# radio-86rk-SRAM-sdcard.net
KiCad netlist of a schematic drawn in EAGLE
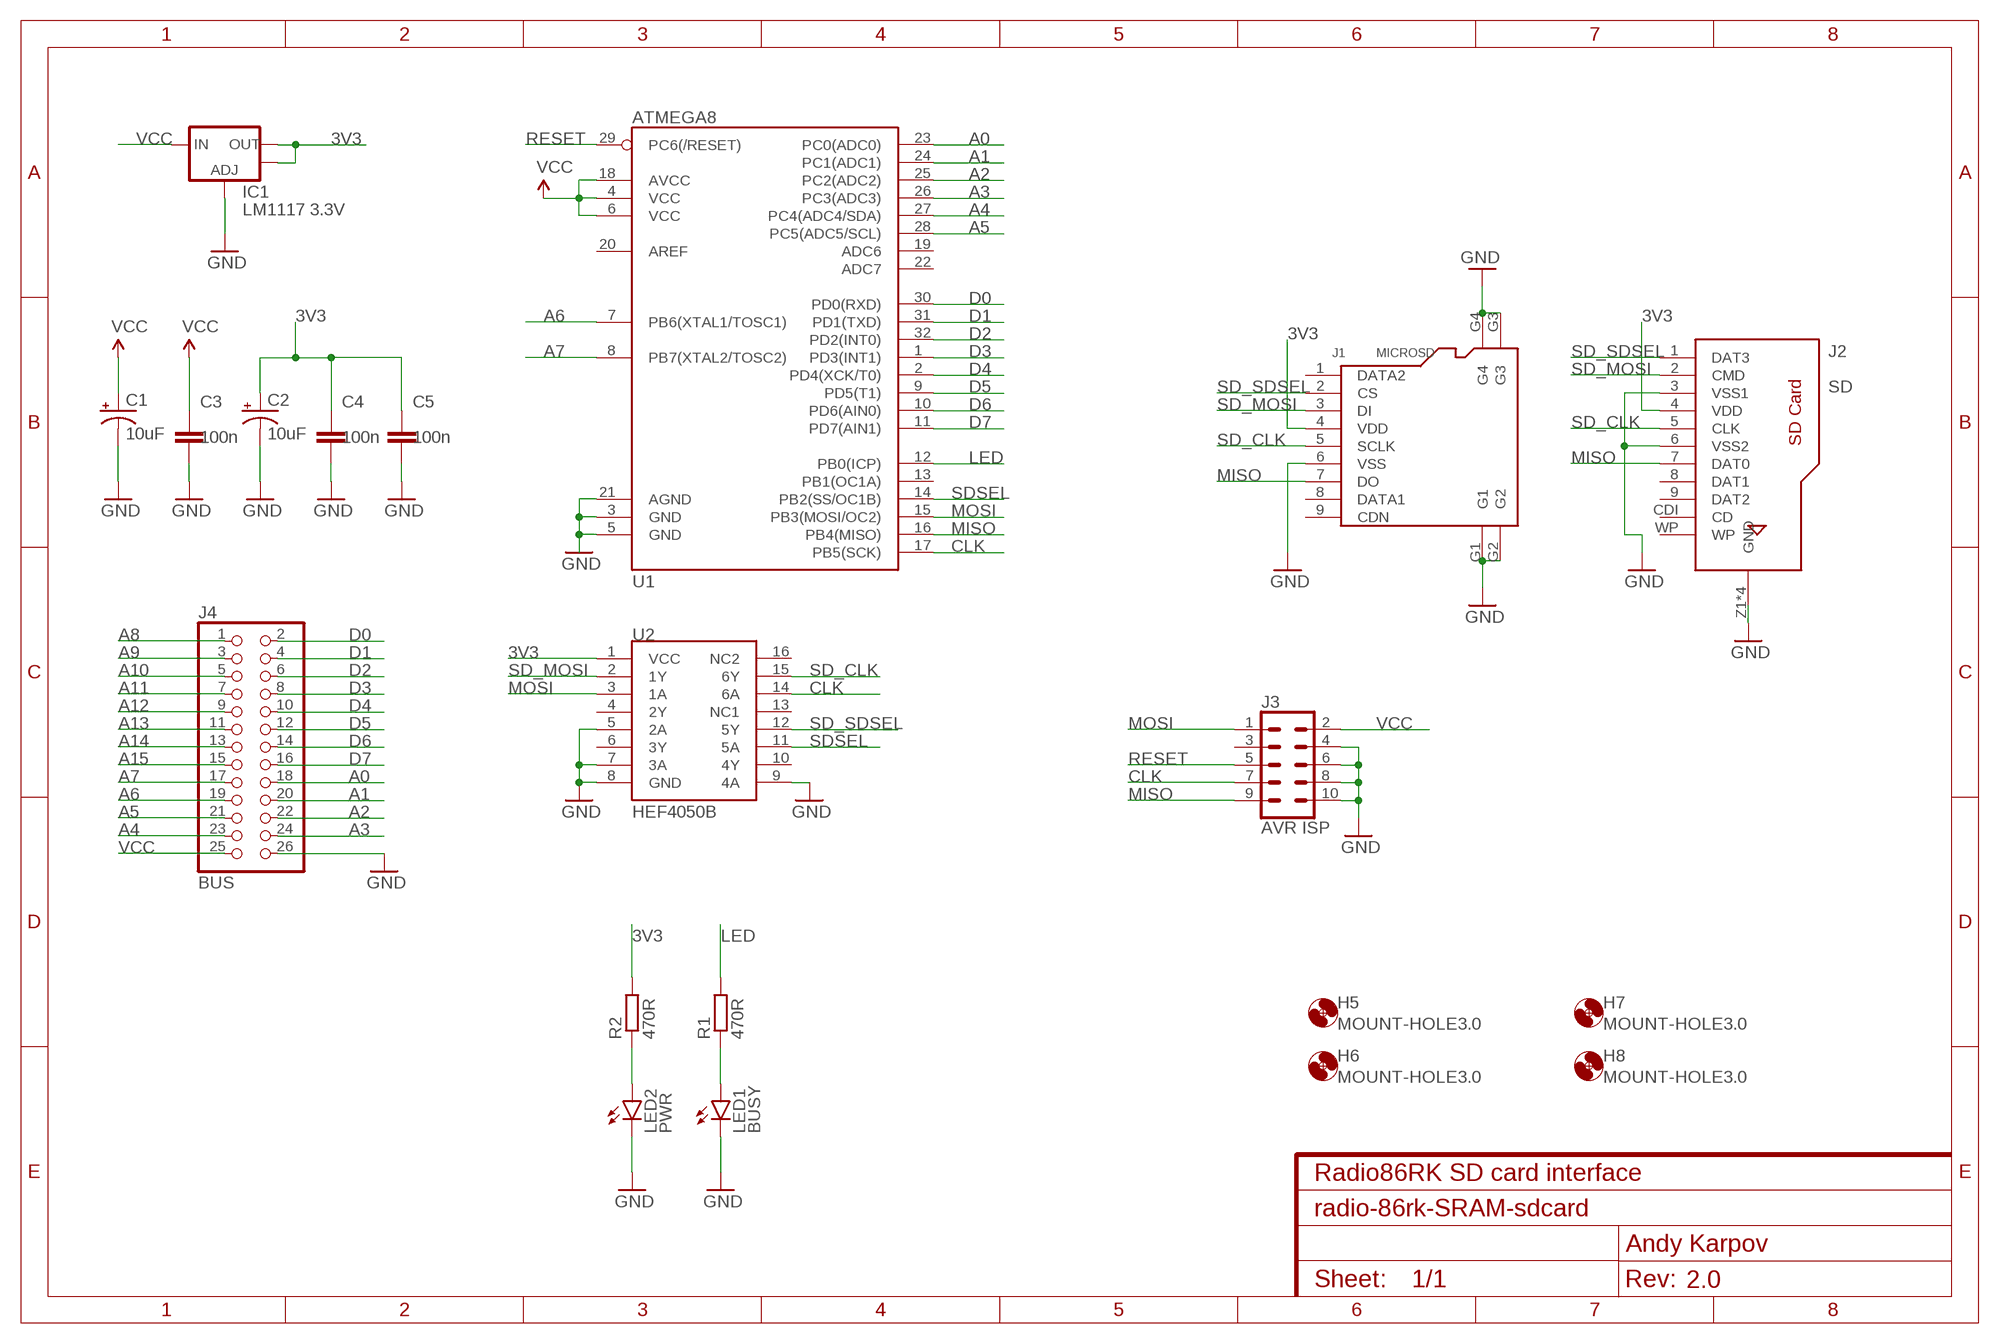
[diagram p0: schematic, sheet 1]

(export (version "E")
  (design (tool "Eeschema 10.0.6"))
  (components
    (comp (ref "C1")
      (value "10uF")
      (footprint "eagle-import:EIA3216")
      (libsource (lib "eagle-import") (part "10UF-16V-10%(TANT)"))
    )
    (comp (ref "C2")
      (value "10uF")
      (footprint "eagle-import:EIA3216")
      (libsource (lib "eagle-import") (part "10UF-16V-10%(TANT)"))
    )
    (comp (ref "C3")
      (value "100n")
      (footprint "eagle-import:C0805")
      (libsource (lib "eagle-import") (part "C-EUC0805"))
    )
    (comp (ref "C4")
      (value "100n")
      (footprint "eagle-import:C0805")
      (libsource (lib "eagle-import") (part "C-EUC0805"))
    )
    (comp (ref "C5")
      (value "100n")
      (footprint "eagle-import:C0805")
      (libsource (lib "eagle-import") (part "C-EUC0805"))
    )
    (comp (ref "H5")
      (value "MOUNT-HOLE3.0")
      (footprint "eagle-import:3,0")
      (libsource (lib "eagle-import") (part "MOUNT-HOLE3.0"))
    )
    (comp (ref "H6")
      (value "MOUNT-HOLE3.0")
      (footprint "eagle-import:3,0")
      (libsource (lib "eagle-import") (part "MOUNT-HOLE3.0"))
    )
    (comp (ref "H7")
      (value "MOUNT-HOLE3.0")
      (footprint "eagle-import:3,0")
      (libsource (lib "eagle-import") (part "MOUNT-HOLE3.0"))
    )
    (comp (ref "H8")
      (value "MOUNT-HOLE3.0")
      (footprint "eagle-import:3,0")
      (libsource (lib "eagle-import") (part "MOUNT-HOLE3.0"))
    )
    (comp (ref "IC1")
      (value "LM1117 3.3V")
      (footprint "eagle-import:SOT223")
      (libsource (lib "eagle-import") (part "V_REG_LM1117SOT223"))
    )
    (comp (ref "J1")
      (value "MICROSD")
      (footprint "eagle-import:MICRO-SD9+4P-SMD-16.1X14.5X1.85MM")
      (libsource (lib "eagle-import") (part "MICRO-SD-CARD-HOLDER-9P"))
    )
    (comp (ref "J2")
      (value "SD")
      (footprint "eagle-import:693063010911")
      (libsource (lib "eagle-import") (part "693063010911"))
    )
    (comp (ref "J3")
      (value "AVR ISP")
      (footprint "eagle-import:2X5-SHROUDED_LOCK")
      (libsource (lib "eagle-import") (part "CONN_05X2SHD_LOCK"))
    )
    (comp (ref "J4")
      (value "BUS")
      (footprint "eagle-import:2X13")
      (libsource (lib "eagle-import") (part "PINHD-2X13"))
    )
    (comp (ref "LED1")
      (value "BUSY")
      (footprint "eagle-import:CHIP-LED0805")
      (libsource (lib "eagle-import") (part "LEDCHIP-LED0805"))
    )
    (comp (ref "LED2")
      (value "PWR")
      (footprint "eagle-import:CHIP-LED0805")
      (libsource (lib "eagle-import") (part "LEDCHIP-LED0805"))
    )
    (comp (ref "R1")
      (value "470R")
      (footprint "eagle-import:R0805")
      (libsource (lib "eagle-import") (part "R-EU_R0805"))
    )
    (comp (ref "R2")
      (value "470R")
      (footprint "eagle-import:R0805")
      (libsource (lib "eagle-import") (part "R-EU_R0805"))
    )
    (comp (ref "U1")
      (value "ATMEGA8")
      (footprint "eagle-import:TQFP32-08")
      (libsource (lib "eagle-import") (part "ATMEGA328_SMT"))
    )
    (comp (ref "U2")
      (value "HEF4050B")
      (footprint "eagle-import:SO16")
      (libsource (lib "eagle-import") (part "HEF4050BSO16"))
    )
  )
  (nets
    (net (code "1") (name "/3V3") (class "Default")
      (node (ref "C2") (pin "A") (pinfunction "+_A") (pintype "passive"))
      (node (ref "C4") (pin "1") (pinfunction "1_1") (pintype "passive"))
      (node (ref "C5") (pin "1") (pinfunction "1_1") (pintype "passive"))
      (node (ref "IC1") (pin "2") (pinfunction "OUT_2") (pintype "output"))
      (node (ref "IC1") (pin "4") (pinfunction "OUT_4") (pintype "output"))
      (node (ref "J1") (pin "4") (pinfunction "VDD_4") (pintype "bidirectional"))
      (node (ref "J2") (pin "4") (pinfunction "VDD_4") (pintype "bidirectional"))
      (node (ref "R2") (pin "2") (pinfunction "2_2") (pintype "passive"))
      (node (ref "U2") (pin "1") (pinfunction "VCC_1") (pintype "power_in"))
    )
    (net (code "2") (name "/A0") (class "Default")
      (node (ref "J4") (pin "18") (pinfunction "18_18") (pintype "passive"))
      (node (ref "U1") (pin "23") (pinfunction "PC0(ADC0)_23") (pintype "bidirectional"))
    )
    (net (code "3") (name "/A1") (class "Default")
      (node (ref "J4") (pin "20") (pinfunction "20_20") (pintype "passive"))
      (node (ref "U1") (pin "24") (pinfunction "PC1(ADC1)_24") (pintype "bidirectional"))
    )
    (net (code "4") (name "/A2") (class "Default")
      (node (ref "J4") (pin "22") (pinfunction "22_22") (pintype "passive"))
      (node (ref "U1") (pin "25") (pinfunction "PC2(ADC2)_25") (pintype "bidirectional"))
    )
    (net (code "5") (name "/A3") (class "Default")
      (node (ref "J4") (pin "24") (pinfunction "24_24") (pintype "passive"))
      (node (ref "U1") (pin "26") (pinfunction "PC3(ADC3)_26") (pintype "bidirectional"))
    )
    (net (code "6") (name "/A4") (class "Default")
      (node (ref "J4") (pin "23") (pinfunction "23_23") (pintype "passive"))
      (node (ref "U1") (pin "27") (pinfunction "PC4(ADC4/SDA)_27") (pintype "bidirectional"))
    )
    (net (code "7") (name "/A5") (class "Default")
      (node (ref "J4") (pin "21") (pinfunction "21_21") (pintype "passive"))
      (node (ref "U1") (pin "28") (pinfunction "PC5(ADC5/SCL)_28") (pintype "bidirectional"))
    )
    (net (code "8") (name "/A6") (class "Default")
      (node (ref "J4") (pin "19") (pinfunction "19_19") (pintype "passive"))
      (node (ref "U1") (pin "7") (pinfunction "PB6(XTAL1/TOSC1)_7") (pintype "bidirectional"))
    )
    (net (code "9") (name "/A7") (class "Default")
      (node (ref "J4") (pin "17") (pinfunction "17_17") (pintype "passive"))
      (node (ref "U1") (pin "8") (pinfunction "PB7(XTAL2/TOSC2)_8") (pintype "bidirectional"))
    )
    (net (code "10") (name "/A8") (class "Default")
      (node (ref "J4") (pin "1") (pinfunction "1_1") (pintype "passive"))
    )
    (net (code "11") (name "/A9") (class "Default")
      (node (ref "J4") (pin "3") (pinfunction "3_3") (pintype "passive"))
    )
    (net (code "12") (name "/A10") (class "Default")
      (node (ref "J4") (pin "5") (pinfunction "5_5") (pintype "passive"))
    )
    (net (code "13") (name "/A11") (class "Default")
      (node (ref "J4") (pin "7") (pinfunction "7_7") (pintype "passive"))
    )
    (net (code "14") (name "/A12") (class "Default")
      (node (ref "J4") (pin "9") (pinfunction "9_9") (pintype "passive"))
    )
    (net (code "15") (name "/A13") (class "Default")
      (node (ref "J4") (pin "11") (pinfunction "11_11") (pintype "passive"))
    )
    (net (code "16") (name "/A14") (class "Default")
      (node (ref "J4") (pin "13") (pinfunction "13_13") (pintype "passive"))
    )
    (net (code "17") (name "/A15") (class "Default")
      (node (ref "J4") (pin "15") (pinfunction "15_15") (pintype "passive"))
    )
    (net (code "18") (name "/CLK") (class "Default")
      (node (ref "J3") (pin "7") (pinfunction "7_7") (pintype "passive"))
      (node (ref "U1") (pin "17") (pinfunction "PB5(SCK)_17") (pintype "bidirectional"))
      (node (ref "U2") (pin "14") (pinfunction "6A_14") (pintype "input"))
    )
    (net (code "19") (name "/D0") (class "Default")
      (node (ref "J4") (pin "2") (pinfunction "2_2") (pintype "passive"))
      (node (ref "U1") (pin "30") (pinfunction "PD0(RXD)_30") (pintype "bidirectional"))
    )
    (net (code "20") (name "/D1") (class "Default")
      (node (ref "J4") (pin "4") (pinfunction "4_4") (pintype "passive"))
      (node (ref "U1") (pin "31") (pinfunction "PD1(TXD)_31") (pintype "bidirectional"))
    )
    (net (code "21") (name "/D2") (class "Default")
      (node (ref "J4") (pin "6") (pinfunction "6_6") (pintype "passive"))
      (node (ref "U1") (pin "32") (pinfunction "PD2(INT0)_32") (pintype "bidirectional"))
    )
    (net (code "22") (name "/D3") (class "Default")
      (node (ref "J4") (pin "8") (pinfunction "8_8") (pintype "passive"))
      (node (ref "U1") (pin "1") (pinfunction "PD3(INT1)_1") (pintype "bidirectional"))
    )
    (net (code "23") (name "/D4") (class "Default")
      (node (ref "J4") (pin "10") (pinfunction "10_10") (pintype "passive"))
      (node (ref "U1") (pin "2") (pinfunction "PD4(XCK/T0)_2") (pintype "bidirectional"))
    )
    (net (code "24") (name "/D5") (class "Default")
      (node (ref "J4") (pin "12") (pinfunction "12_12") (pintype "passive"))
      (node (ref "U1") (pin "9") (pinfunction "PD5(T1)_9") (pintype "bidirectional"))
    )
    (net (code "25") (name "/D6") (class "Default")
      (node (ref "J4") (pin "14") (pinfunction "14_14") (pintype "passive"))
      (node (ref "U1") (pin "10") (pinfunction "PD6(AIN0)_10") (pintype "bidirectional"))
    )
    (net (code "26") (name "/D7") (class "Default")
      (node (ref "J4") (pin "16") (pinfunction "16_16") (pintype "passive"))
      (node (ref "U1") (pin "11") (pinfunction "PD7(AIN1)_11") (pintype "bidirectional"))
    )
    (net (code "27") (name "/LED") (class "Default")
      (node (ref "R1") (pin "2") (pinfunction "2_2") (pintype "passive"))
      (node (ref "U1") (pin "12") (pinfunction "PB0(ICP)_12") (pintype "bidirectional"))
    )
    (net (code "28") (name "/MISO") (class "Default")
      (node (ref "J1") (pin "7") (pinfunction "DO_7") (pintype "bidirectional"))
      (node (ref "J2") (pin "7") (pinfunction "DAT0_7") (pintype "bidirectional"))
      (node (ref "J3") (pin "9") (pinfunction "9_9") (pintype "passive"))
      (node (ref "U1") (pin "16") (pinfunction "PB4(MISO)_16") (pintype "bidirectional"))
    )
    (net (code "29") (name "/MOSI") (class "Default")
      (node (ref "J3") (pin "1") (pinfunction "1_1") (pintype "passive"))
      (node (ref "U1") (pin "15") (pinfunction "PB3(MOSI/OC2)_15") (pintype "bidirectional"))
      (node (ref "U2") (pin "3") (pinfunction "1A_3") (pintype "input"))
    )
    (net (code "30") (name "/RESET") (class "Default")
      (node (ref "J3") (pin "5") (pinfunction "5_5") (pintype "passive"))
      (node (ref "U1") (pin "29") (pinfunction "PC6(/RESET)_29") (pintype "bidirectional"))
    )
    (net (code "31") (name "/SDSEL") (class "Default")
      (node (ref "U1") (pin "14") (pinfunction "PB2(SS/OC1B)_14") (pintype "bidirectional"))
      (node (ref "U2") (pin "11") (pinfunction "5A_11") (pintype "input"))
    )
    (net (code "32") (name "/SD_CLK") (class "Default")
      (node (ref "J1") (pin "5") (pinfunction "SCLK_5") (pintype "bidirectional"))
      (node (ref "J2") (pin "5") (pinfunction "CLK_5") (pintype "bidirectional"))
      (node (ref "U2") (pin "15") (pinfunction "6Y_15") (pintype "output"))
    )
    (net (code "33") (name "/SD_MOSI") (class "Default")
      (node (ref "J1") (pin "3") (pinfunction "DI_3") (pintype "bidirectional"))
      (node (ref "J2") (pin "2") (pinfunction "CMD_2") (pintype "bidirectional"))
      (node (ref "U2") (pin "2") (pinfunction "1Y_2") (pintype "output"))
    )
    (net (code "34") (name "/SD_SDSEL") (class "Default")
      (node (ref "J1") (pin "2") (pinfunction "CS_2") (pintype "bidirectional"))
      (node (ref "J2") (pin "1") (pinfunction "DAT3_1") (pintype "bidirectional"))
      (node (ref "U2") (pin "12") (pinfunction "5Y_12") (pintype "output"))
    )
    (net (code "35") (name "GND") (class "Default")
      (node (ref "C1") (pin "C") (pinfunction "-_C") (pintype "passive"))
      (node (ref "C2") (pin "C") (pinfunction "-_C") (pintype "passive"))
      (node (ref "C3") (pin "2") (pinfunction "2_2") (pintype "passive"))
      (node (ref "C4") (pin "2") (pinfunction "2_2") (pintype "passive"))
      (node (ref "C5") (pin "2") (pinfunction "2_2") (pintype "passive"))
      (node (ref "IC1") (pin "1") (pinfunction "ADJ_1") (pintype "input"))
      (node (ref "J1") (pin "6") (pinfunction "VSS_6") (pintype "bidirectional"))
      (node (ref "J1") (pin "G1") (pinfunction "G1_G1") (pintype "bidirectional"))
      (node (ref "J1") (pin "G2") (pinfunction "G2_G2") (pintype "bidirectional"))
      (node (ref "J1") (pin "G3") (pinfunction "G3_G3") (pintype "bidirectional"))
      (node (ref "J1") (pin "G4") (pinfunction "G4_G4") (pintype "bidirectional"))
      (node (ref "J2") (pin "3") (pinfunction "VSS1_3") (pintype "bidirectional"))
      (node (ref "J2") (pin "6") (pinfunction "VSS2_6") (pintype "bidirectional"))
      (node (ref "J2") (pin "Z1") (pinfunction "GND_Z1") (pintype "bidirectional"))
      (node (ref "J2") (pin "Z2") (pinfunction "GND_Z2") (pintype "bidirectional"))
      (node (ref "J2") (pin "Z3") (pinfunction "GND_Z3") (pintype "bidirectional"))
      (node (ref "J2") (pin "Z4") (pinfunction "GND_Z4") (pintype "bidirectional"))
      (node (ref "J3") (pin "10") (pinfunction "10_10") (pintype "passive"))
      (node (ref "J3") (pin "4") (pinfunction "4_4") (pintype "passive"))
      (node (ref "J3") (pin "6") (pinfunction "6_6") (pintype "passive"))
      (node (ref "J3") (pin "8") (pinfunction "8_8") (pintype "passive"))
      (node (ref "J4") (pin "26") (pinfunction "26_26") (pintype "passive"))
      (node (ref "LED1") (pin "C") (pinfunction "C_C") (pintype "passive"))
      (node (ref "LED2") (pin "C") (pinfunction "C_C") (pintype "passive"))
      (node (ref "U1") (pin "21") (pinfunction "AGND_21") (pintype "bidirectional"))
      (node (ref "U1") (pin "3") (pinfunction "GND_3") (pintype "bidirectional"))
      (node (ref "U1") (pin "5") (pinfunction "GND_5") (pintype "bidirectional"))
      (node (ref "U2") (pin "5") (pinfunction "2A_5") (pintype "input"))
      (node (ref "U2") (pin "7") (pinfunction "3A_7") (pintype "input"))
      (node (ref "U2") (pin "8") (pinfunction "GND_8") (pintype "power_in"))
      (node (ref "U2") (pin "9") (pinfunction "4A_9") (pintype "input"))
    )
    (net (code "36") (name "Net-(LED1-PadA)") (class "Default")
      (node (ref "LED1") (pin "A") (pinfunction "A_A") (pintype "passive"))
      (node (ref "R1") (pin "1") (pinfunction "1_1") (pintype "passive"))
    )
    (net (code "37") (name "Net-(LED2-PadA)") (class "Default")
      (node (ref "LED2") (pin "A") (pinfunction "A_A") (pintype "passive"))
      (node (ref "R2") (pin "1") (pinfunction "1_1") (pintype "passive"))
    )
    (net (code "38") (name "VCC") (class "Default")
      (node (ref "C1") (pin "A") (pinfunction "+_A") (pintype "passive"))
      (node (ref "C3") (pin "1") (pinfunction "1_1") (pintype "passive"))
      (node (ref "IC1") (pin "3") (pinfunction "IN_3") (pintype "input"))
      (node (ref "J3") (pin "2") (pinfunction "2_2") (pintype "passive"))
      (node (ref "J4") (pin "25") (pinfunction "25_25") (pintype "passive"))
      (node (ref "U1") (pin "18") (pinfunction "AVCC_18") (pintype "bidirectional"))
      (node (ref "U1") (pin "4") (pinfunction "VCC_4") (pintype "bidirectional"))
      (node (ref "U1") (pin "6") (pinfunction "VCC_6") (pintype "bidirectional"))
    )
    (net (code "39") (name "unconnected-(J1-CDN-Pad9)") (class "Default")
      (node (ref "J1") (pin "9") (pinfunction "CDN_9") (pintype "bidirectional"))
    )
    (net (code "40") (name "unconnected-(J1-DATA1-Pad8)") (class "Default")
      (node (ref "J1") (pin "8") (pinfunction "DATA1_8") (pintype "bidirectional"))
    )
    (net (code "41") (name "unconnected-(J1-DATA2-Pad1)") (class "Default")
      (node (ref "J1") (pin "1") (pinfunction "DATA2_1") (pintype "bidirectional"))
    )
    (net (code "42") (name "unconnected-(J2-CD-PadCDI)") (class "Default")
      (node (ref "J2") (pin "CDI") (pinfunction "CD_CDI") (pintype "bidirectional"))
    )
    (net (code "43") (name "unconnected-(J2-DAT1-Pad8)") (class "Default")
      (node (ref "J2") (pin "8") (pinfunction "DAT1_8") (pintype "bidirectional"))
    )
    (net (code "44") (name "unconnected-(J2-DAT2-Pad9)") (class "Default")
      (node (ref "J2") (pin "9") (pinfunction "DAT2_9") (pintype "bidirectional"))
    )
    (net (code "45") (name "unconnected-(J2-PadWP)") (class "Default")
      (node (ref "J2") (pin "WP") (pinfunction "WP_WP") (pintype "bidirectional"))
    )
    (net (code "46") (name "unconnected-(J3-Pad3)") (class "Default")
      (node (ref "J3") (pin "3") (pinfunction "3_3") (pintype "passive"))
    )
    (net (code "47") (name "unconnected-(U1-ADC6-Pad19)") (class "Default")
      (node (ref "U1") (pin "19") (pinfunction "ADC6_19") (pintype "bidirectional"))
    )
    (net (code "48") (name "unconnected-(U1-ADC7-Pad22)") (class "Default")
      (node (ref "U1") (pin "22") (pinfunction "ADC7_22") (pintype "bidirectional"))
    )
    (net (code "49") (name "unconnected-(U1-AREF-Pad20)") (class "Default")
      (node (ref "U1") (pin "20") (pinfunction "AREF_20") (pintype "bidirectional"))
    )
    (net (code "50") (name "unconnected-(U1-PB1(OC1A)-Pad13)") (class "Default")
      (node (ref "U1") (pin "13") (pinfunction "PB1(OC1A)_13") (pintype "bidirectional"))
    )
    (net (code "51") (name "unconnected-(U2-2Y-Pad4)") (class "Default")
      (node (ref "U2") (pin "4") (pinfunction "2Y_4") (pintype "output"))
    )
    (net (code "52") (name "unconnected-(U2-3Y-Pad6)") (class "Default")
      (node (ref "U2") (pin "6") (pinfunction "3Y_6") (pintype "output"))
    )
    (net (code "53") (name "unconnected-(U2-4Y-Pad10)") (class "Default")
      (node (ref "U2") (pin "10") (pinfunction "4Y_10") (pintype "output"))
    )
    (net (code "54") (name "unconnected-(U2-NC1-Pad13)") (class "Default")
      (node (ref "U2") (pin "13") (pinfunction "NC1_13") (pintype "no_connect"))
    )
    (net (code "55") (name "unconnected-(U2-NC2-Pad16)") (class "Default")
      (node (ref "U2") (pin "16") (pinfunction "NC2_16") (pintype "no_connect"))
    )
  )
)
